# TIDA-00830_MSP430F2617.net
KiCad netlist of a schematic drawn in Altium Designer
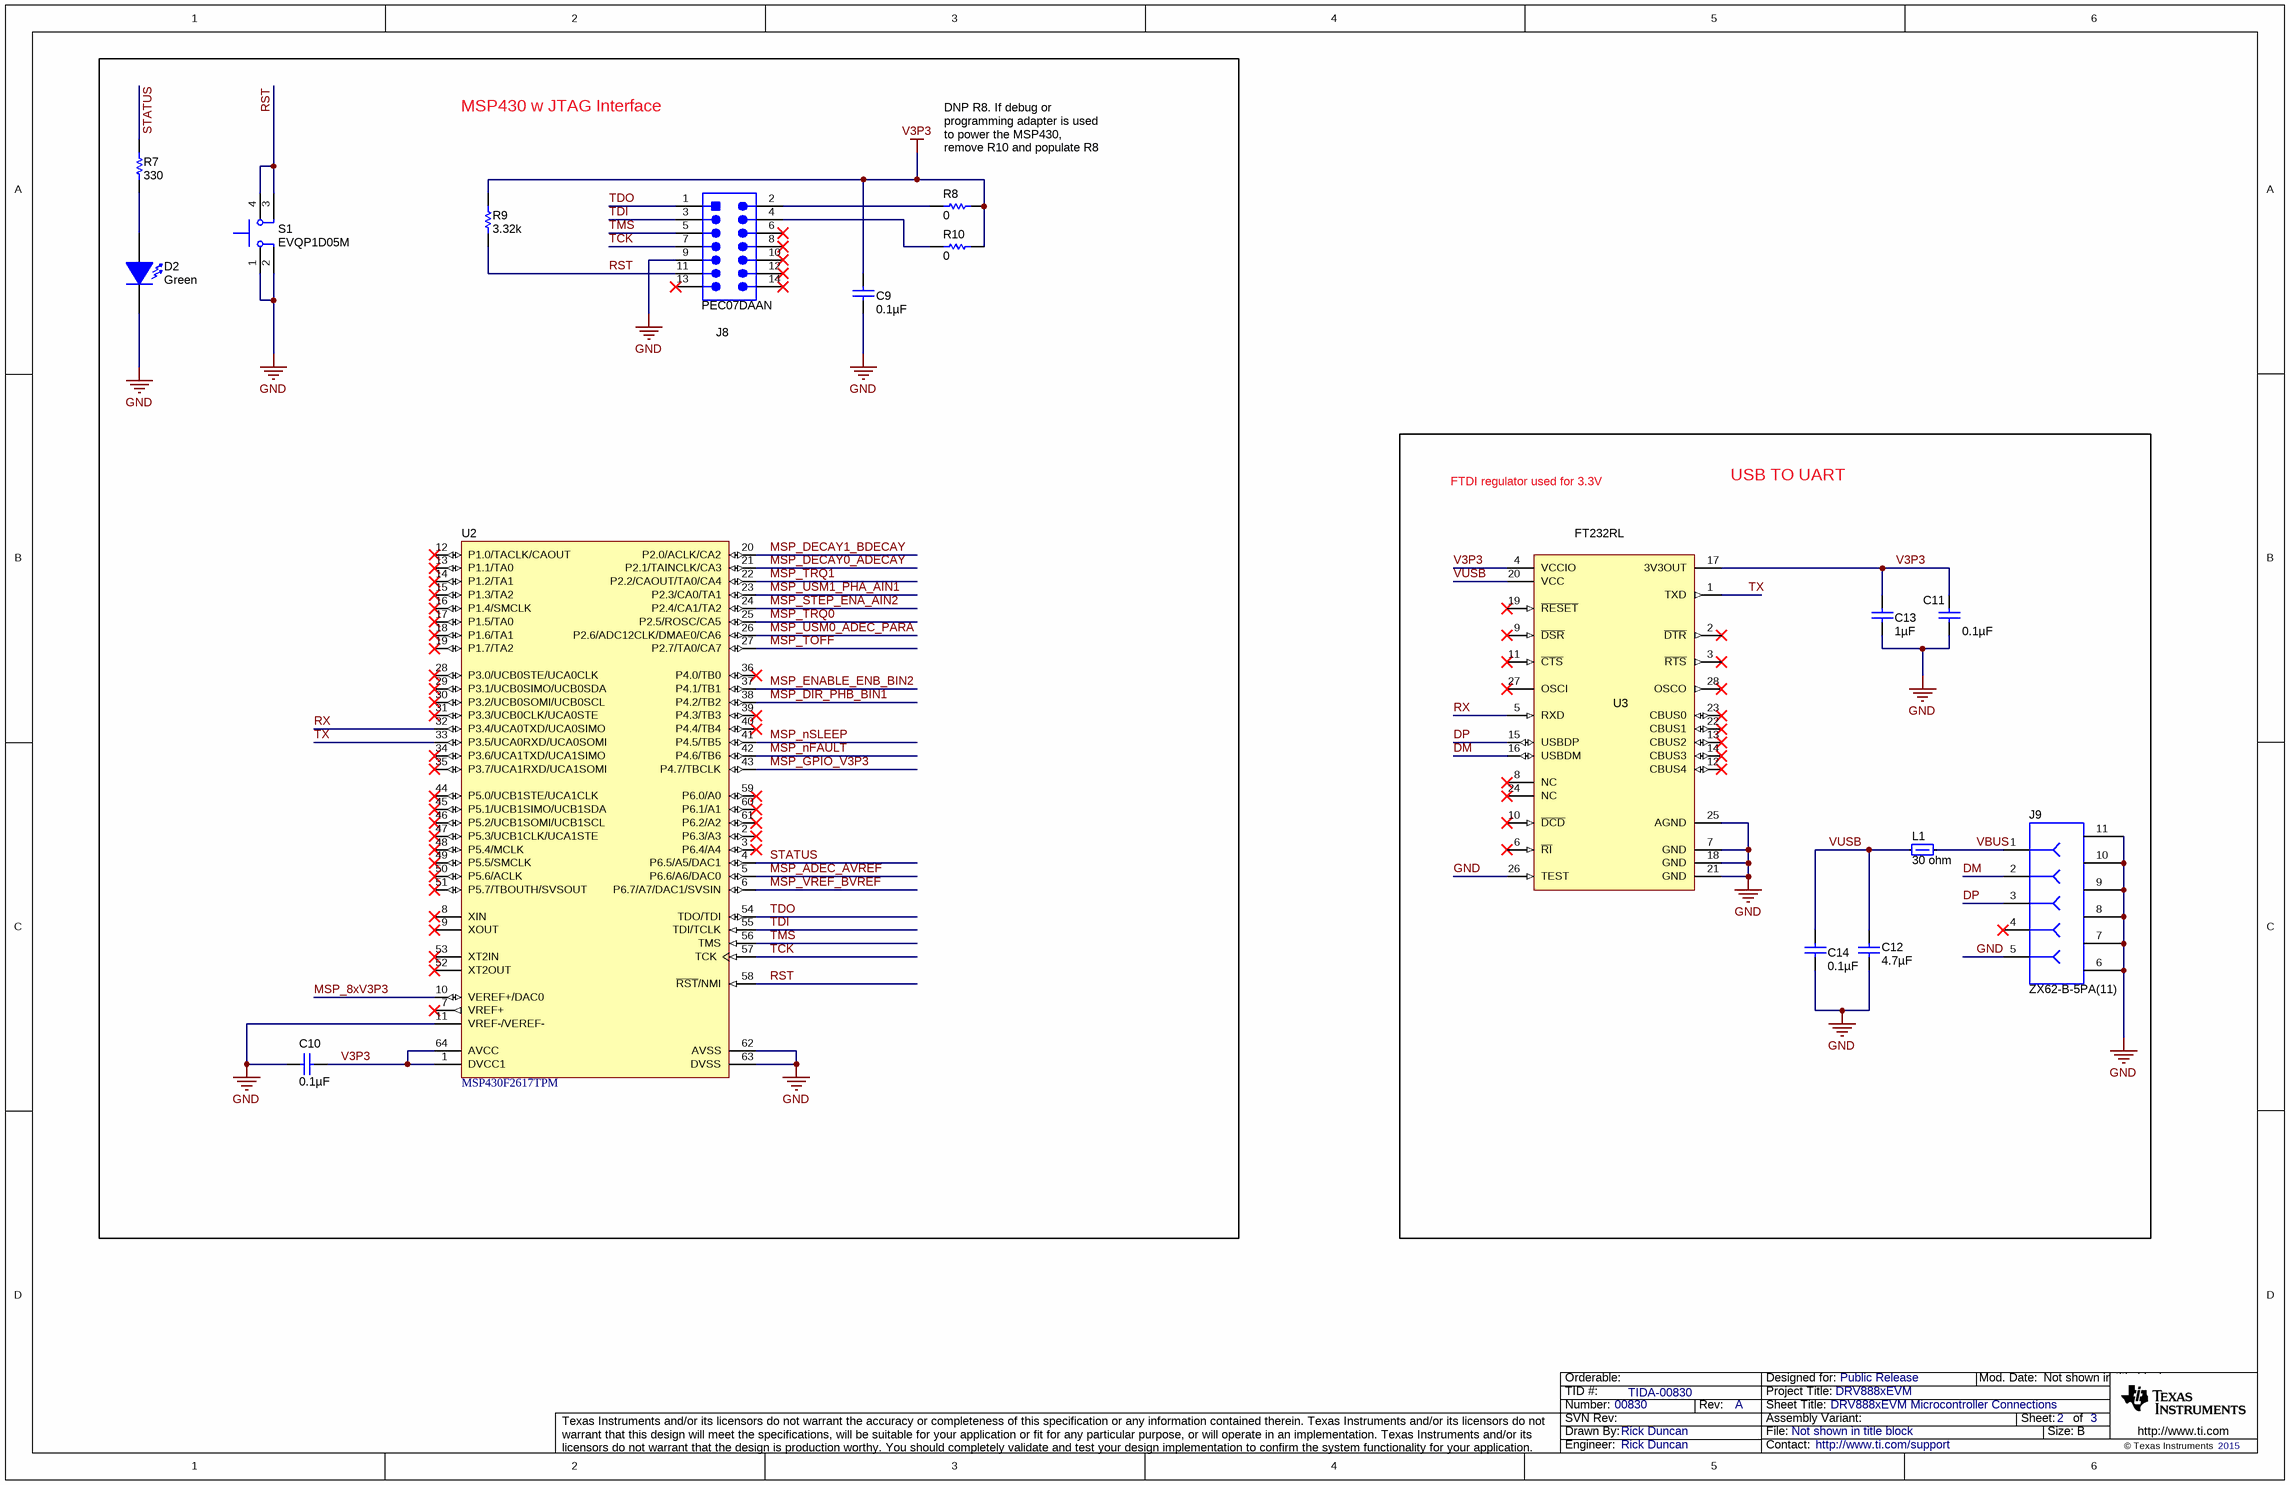
[diagram p0: TIDA-00830_MSP430F2617.SchDoc]

(export (version "E")
  (design (tool "Eeschema 10.0.6"))
  (components
    (comp (ref "C9")
      (value "GRM155R61A104KA01D")
      (footprint "0402L")
      (description "CAP, CERM, 0.1 µF, 10 V, +/- 10%, X5R, 0402")
      (fields
        (field (name "MANUFACTURER") "MuRata")
        (field (name "VALUEDISPLAYED") "0.1µF")
        (field (name "PUBLISHER") "Texas Instruments")
      )
      (libsource (lib "Capacitor_Ceramic") (part "GRM155R61A104KA01D"))
    )
    (comp (ref "C10")
      (value "GRM155R61A104KA01D")
      (footprint "0402L")
      (description "CAP, CERM, 0.1 µF, 10 V, +/- 10%, X5R, 0402")
      (fields
        (field (name "MANUFACTURER") "MuRata")
        (field (name "VALUEDISPLAYED") "0.1µF")
        (field (name "PUBLISHER") "Texas Instruments")
      )
      (libsource (lib "Capacitor_Ceramic") (part "GRM155R61A104KA01D"))
    )
    (comp (ref "C11")
      (value "GRM155R61A104KA01D")
      (footprint "0402L")
      (description "CAP, CERM, 0.1 µF, 10 V, +/- 10%, X5R, 0402")
      (fields
        (field (name "MANUFACTURER") "MuRata")
        (field (name "VALUEDISPLAYED") "0.1µF")
        (field (name "PUBLISHER") "Texas Instruments")
      )
      (libsource (lib "Capacitor_Ceramic") (part "GRM155R61A104KA01D"))
    )
    (comp (ref "C12")
      (value "CGB3B1X5R1A475K055AC")
      (footprint "0603L")
      (description "CAP, CERM, 4.7 µF, 10 V, +/- 10%, X5R, 0603")
      (fields
        (field (name "VALUEDISPLAYED") "4.7µF")
        (field (name "MANUFACTURER") "TDK")
        (field (name "PUBLISHER") "Texas Instruments")
      )
      (libsource (lib "Capacitor_Ceramic") (part "CGB3B1X5R1A475K055AC"))
    )
    (comp (ref "C13")
      (value "GRM155R61A105KE15D")
      (footprint "0402L")
      (description "CAP, CERM, 1 µF, 10 V, +/- 10%, X5R, 0402")
      (fields
        (field (name "MANUFACTURER") "MuRata")
        (field (name "VALUEDISPLAYED") "1µF")
        (field (name "PUBLISHER") "Texas Instruments")
      )
      (libsource (lib "Capacitor_Ceramic") (part "GRM155R61A105KE15D"))
    )
    (comp (ref "C14")
      (value "GRM155R61A104KA01D")
      (footprint "0402L")
      (description "CAP, CERM, 0.1 µF, 10 V, +/- 10%, X5R, 0402")
      (fields
        (field (name "MANUFACTURER") "MuRata")
        (field (name "VALUEDISPLAYED") "0.1µF")
        (field (name "PUBLISHER") "Texas Instruments")
      )
      (libsource (lib "Capacitor_Ceramic") (part "GRM155R61A104KA01D"))
    )
    (comp (ref "D2")
      (value "Green")
      (footprint "LED_LTST-C190")
      (description "LED, Green, SMD")
      (fields
        (field (name "MANUFACTURER") "Lite-On")
        (field (name "PARTNUMBER") "LTST-C190GKT")
        (field (name "PUBLISHER") "Texas Instruments")
      )
      (libsource (lib "LED") (part "LTST-C190GKT"))
    )
    (comp (ref "J8")
      (value "PEC07DAAN")
      (footprint "CONN_PEC07DAAN")
      (description "Header, 100mil, 7x2, Tin, TH")
      (fields
        (field (name "MANUFACTURER") "Sullins Connector Solutions")
        (field (name "SYMBOLCREATOR") "a0412235")
        (field (name "PUBLISHER") "Texas Instruments")
      )
      (libsource (lib "Connectors_Sullins") (part "PEC07DAAN"))
    )
    (comp (ref "J9")
      (value "ZX62-B-5PA(11)")
      (footprint "CONN_USB_micro_ZX62-B-5PA")
      (description "Connector, Receptacle, Micro-USB Type B, R/A, Bottom Mount SMT")
      (fields
        (field (name "MANUFACTURER") "Hirose Electric Co. Ltd.")
        (field (name "SYMBOLCREATOR") "a0411947")
        (field (name "PUBLISHER") "Texas Instruments")
      )
      (libsource (lib "Connectors_Other") (part "ZX62-B-5PA(11)"))
    )
    (comp (ref "L1")
      (value "30 ohm")
      (footprint "0805L")
      (description "Ferrite Bead, 30 ohm @ 100 MHz, 1.5 A, 0805")
      (fields
        (field (name "MANUFACTURER") "TDK")
        (field (name "PARTNUMBER") "MMZ2012R300A")
        (field (name "PUBLISHER") "Texas Instruments")
      )
      (libsource (lib "FerriteBead") (part "MMZ2012R300A"))
    )
    (comp (ref "R7")
      (value "330")
      (footprint "0402L")
      (description "RES, 330, 5%, 0.063 W, 0402")
      (fields
        (field (name "MANUFACTURER") "Vishay-Dale")
        (field (name "PARTNUMBER") "CRCW0402330RJNED")
        (field (name "PUBLISHER") "Texas Instruments")
      )
      (libsource (lib "Resistor_0402") (part "CRCW0402330RJNED"))
    )
    (comp (ref "R8")
      (value "0")
      (footprint "0402L")
      (description "RES, 0, 5%, 0.063 W, 0402")
      (fields
        (field (name "MANUFACTURER") "Panasonic")
        (field (name "PARTNUMBER") "ERJ-2GE0R00X")
        (field (name "PUBLISHER") "Texas Instruments")
      )
      (libsource (lib "Resistor_0402") (part "ERJ-2GE0R00X"))
    )
    (comp (ref "R9")
      (value "3.32k")
      (footprint "0402L")
      (description "RES, 3.32 k, 1%, 0.063 W, 0402")
      (fields
        (field (name "MANUFACTURER") "Vishay-Dale")
        (field (name "PARTNUMBER") "CRCW04023K32FKED")
        (field (name "PUBLISHER") "Texas Instruments")
      )
      (libsource (lib "Resistor_0402") (part "CRCW04023K32FKED"))
    )
    (comp (ref "R10")
      (value "0")
      (footprint "0402L")
      (description "RES, 0, 5%, 0.063 W, 0402")
      (fields
        (field (name "MANUFACTURER") "Panasonic")
        (field (name "PARTNUMBER") "ERJ-2GE0R00X")
        (field (name "PUBLISHER") "Texas Instruments")
      )
      (libsource (lib "Resistor_0402") (part "ERJ-2GE0R00X"))
    )
    (comp (ref "S1")
      (value "EVQP1D05M")
      (footprint "SW_EVQxxx05M")
      (description "Switch, Tactile, SPST-NO, 0.05A, 12V, SMT")
      (fields
        (field (name "MANUFACTURER") "Panasonic")
        (field (name "SYMBOLCREATOR") "a0799628")
        (field (name "PUBLISHER") "Texas Instruments")
      )
      (libsource (lib "Switches") (part "EVQP1D05M"))
    )
    (comp (ref "U2")
      (value "MSP430F2617TPM")
      (footprint "PM0064A_L")
      (fields
        (field (name "MANUFACTURER") "Texas Instruments")
        (field (name "ALTERNATE PARTNUMBER") "Equivalent")
      )
      (libsource (lib "TI MCU MSP430") (part "MSP430F2617TPM"))
    )
    (comp (ref "U3")
      (value "FT232RL")
      (footprint "SSOP28_M")
      (description "USB to Serial UART, SSOP28")
      (fields
        (field (name "MANUFACTURER") "FTDI")
        (field (name "SYMBOLCREATOR") "x0208326")
        (field (name "PUBLISHER") "Texas Instruments")
      )
      (libsource (lib "Other_IC") (part "FT232RL"))
    )
  )
  (nets
    (net (code "1") (name "/DM") (class "Default")
      (node (ref "J9") (pin "2") (pinfunction "2_2") (pintype "passive"))
      (node (ref "U3") (pin "16") (pinfunction "USBDM_16") (pintype "bidirectional"))
    )
    (net (code "2") (name "/DP") (class "Default")
      (node (ref "J9") (pin "3") (pinfunction "3_3") (pintype "passive"))
      (node (ref "U3") (pin "15") (pinfunction "USBDP_15") (pintype "bidirectional"))
    )
    (net (code "3") (name "/MSP_8xV3P3") (class "Default")
      (node (ref "U2") (pin "10") (pinfunction "VEREF+/DAC0_10") (pintype "bidirectional"))
    )
    (net (code "4") (name "/MSP_ADEC_AVREF") (class "Default")
      (node (ref "U2") (pin "5") (pinfunction "P6.6/A6/DAC0_5") (pintype "bidirectional"))
    )
    (net (code "5") (name "/MSP_DECAY0_ADECAY") (class "Default")
      (node (ref "U2") (pin "21") (pinfunction "P2.1/TAINCLK/CA3_21") (pintype "bidirectional"))
    )
    (net (code "6") (name "/MSP_DECAY1_BDECAY") (class "Default")
      (node (ref "U2") (pin "20") (pinfunction "P2.0/ACLK/CA2_20") (pintype "bidirectional"))
    )
    (net (code "7") (name "/MSP_DIR_PHB_BIN1") (class "Default")
      (node (ref "U2") (pin "38") (pinfunction "P4.2/TB2_38") (pintype "bidirectional"))
    )
    (net (code "8") (name "/MSP_ENABLE_ENB_BIN2") (class "Default")
      (node (ref "U2") (pin "37") (pinfunction "P4.1/TB1_37") (pintype "bidirectional"))
    )
    (net (code "9") (name "/MSP_GPIO_V3P3") (class "Default")
      (node (ref "U2") (pin "43") (pinfunction "P4.7/TBCLK_43") (pintype "bidirectional"))
    )
    (net (code "10") (name "/MSP_STEP_ENA_AIN2") (class "Default")
      (node (ref "U2") (pin "24") (pinfunction "P2.4/CA1/TA2_24") (pintype "bidirectional"))
    )
    (net (code "11") (name "/MSP_TOFF") (class "Default")
      (node (ref "U2") (pin "27") (pinfunction "P2.7/TA0/CA7_27") (pintype "bidirectional"))
    )
    (net (code "12") (name "/MSP_TRQ0") (class "Default")
      (node (ref "U2") (pin "25") (pinfunction "P2.5/ROSC/CA5_25") (pintype "bidirectional"))
    )
    (net (code "13") (name "/MSP_TRQ1") (class "Default")
      (node (ref "U2") (pin "22") (pinfunction "P2.2/CAOUT/TA0/CA4_22") (pintype "bidirectional"))
    )
    (net (code "14") (name "/MSP_USM0_ADEC_PARA") (class "Default")
      (node (ref "U2") (pin "26") (pinfunction "P2.6/ADC12CLK/DMAE0/CA6_26") (pintype "bidirectional"))
    )
    (net (code "15") (name "/MSP_USM1_PHA_AIN1") (class "Default")
      (node (ref "U2") (pin "23") (pinfunction "P2.3/CA0/TA1_23") (pintype "bidirectional"))
    )
    (net (code "16") (name "/MSP_VREF_BVREF") (class "Default")
      (node (ref "U2") (pin "6") (pinfunction "P6.7/A7/DAC1/SVSIN_6") (pintype "bidirectional"))
    )
    (net (code "17") (name "/MSP_nFAULT") (class "Default")
      (node (ref "U2") (pin "42") (pinfunction "P4.6/TB6_42") (pintype "bidirectional"))
    )
    (net (code "18") (name "/MSP_nSLEEP") (class "Default")
      (node (ref "U2") (pin "41") (pinfunction "P4.5/TB5_41") (pintype "bidirectional"))
    )
    (net (code "19") (name "/RST") (class "Default")
      (node (ref "J8") (pin "11") (pinfunction "11_11") (pintype "passive"))
      (node (ref "R9") (pin "1") (pinfunction "1_1") (pintype "passive"))
      (node (ref "S1") (pin "3") (pinfunction "3_3") (pintype "passive"))
      (node (ref "S1") (pin "4") (pinfunction "4_4") (pintype "passive"))
      (node (ref "U2") (pin "58") (pinfunction "~{RST}/NMI_58") (pintype "input"))
    )
    (net (code "20") (name "/RX") (class "Default")
      (node (ref "U2") (pin "32") (pinfunction "P3.4/UCA0TXD/UCA0SIMO_32") (pintype "bidirectional"))
      (node (ref "U3") (pin "5") (pinfunction "RXD_5") (pintype "input"))
    )
    (net (code "21") (name "/STATUS") (class "Default")
      (node (ref "R7") (pin "2") (pinfunction "2_2") (pintype "passive"))
      (node (ref "U2") (pin "4") (pinfunction "P6.5/A5/DAC1_4") (pintype "bidirectional"))
    )
    (net (code "22") (name "/TCK") (class "Default")
      (node (ref "J8") (pin "7") (pinfunction "7_7") (pintype "passive"))
      (node (ref "U2") (pin "57") (pinfunction "TCK_57") (pintype "input"))
    )
    (net (code "23") (name "/TDI") (class "Default")
      (node (ref "J8") (pin "3") (pinfunction "3_3") (pintype "passive"))
      (node (ref "U2") (pin "55") (pinfunction "TDI/TCLK_55") (pintype "input"))
    )
    (net (code "24") (name "/TDO") (class "Default")
      (node (ref "J8") (pin "1") (pinfunction "1_1") (pintype "passive"))
      (node (ref "U2") (pin "54") (pinfunction "TDO/TDI_54") (pintype "bidirectional"))
    )
    (net (code "25") (name "/TMS") (class "Default")
      (node (ref "J8") (pin "5") (pinfunction "5_5") (pintype "passive"))
      (node (ref "U2") (pin "56") (pinfunction "TMS_56") (pintype "input"))
    )
    (net (code "26") (name "/TX") (class "Default")
      (node (ref "U2") (pin "33") (pinfunction "P3.5/UCA0RXD/UCA0SOMI_33") (pintype "bidirectional"))
      (node (ref "U3") (pin "1") (pinfunction "TXD_1") (pintype "output"))
    )
    (net (code "27") (name "/VBUS") (class "Default")
      (node (ref "J9") (pin "1") (pinfunction "1_1") (pintype "passive"))
      (node (ref "L1") (pin "2") (pinfunction "2_2") (pintype "passive"))
    )
    (net (code "28") (name "/VUSB") (class "Default")
      (node (ref "C12") (pin "1") (pinfunction "1_1") (pintype "passive"))
      (node (ref "C14") (pin "1") (pinfunction "1_1") (pintype "passive"))
      (node (ref "L1") (pin "1") (pinfunction "1_1") (pintype "passive"))
      (node (ref "U3") (pin "20") (pinfunction "VCC_20") (pintype "power_in"))
    )
    (net (code "29") (name "GND") (class "Default")
      (node (ref "C10") (pin "2") (pinfunction "2_2") (pintype "passive"))
      (node (ref "C11") (pin "2") (pinfunction "2_2") (pintype "passive"))
      (node (ref "C12") (pin "2") (pinfunction "2_2") (pintype "passive"))
      (node (ref "C13") (pin "2") (pinfunction "2_2") (pintype "passive"))
      (node (ref "C14") (pin "2") (pinfunction "2_2") (pintype "passive"))
      (node (ref "C9") (pin "2") (pinfunction "2_2") (pintype "passive"))
      (node (ref "D2") (pin "2") (pinfunction "K_2") (pintype "passive"))
      (node (ref "J8") (pin "9") (pinfunction "9_9") (pintype "passive"))
      (node (ref "J9") (pin "10") (pinfunction "10_10") (pintype "passive"))
      (node (ref "J9") (pin "11") (pinfunction "11_11") (pintype "passive"))
      (node (ref "J9") (pin "5") (pinfunction "5_5") (pintype "passive"))
      (node (ref "J9") (pin "6") (pinfunction "6_6") (pintype "passive"))
      (node (ref "J9") (pin "7") (pinfunction "7_7") (pintype "passive"))
      (node (ref "J9") (pin "8") (pinfunction "8_8") (pintype "passive"))
      (node (ref "J9") (pin "9") (pinfunction "9_9") (pintype "passive"))
      (node (ref "S1") (pin "1") (pinfunction "1_1") (pintype "passive"))
      (node (ref "S1") (pin "2") (pinfunction "2_2") (pintype "passive"))
      (node (ref "U2") (pin "11") (pinfunction "VREF-/VEREF-_11") (pintype "passive"))
      (node (ref "U2") (pin "62") (pinfunction "AVSS_62") (pintype "power_in"))
      (node (ref "U2") (pin "63") (pinfunction "DVSS_63") (pintype "power_in"))
      (node (ref "U3") (pin "18") (pinfunction "GND_18") (pintype "power_in"))
      (node (ref "U3") (pin "21") (pinfunction "GND_21") (pintype "power_in"))
      (node (ref "U3") (pin "25") (pinfunction "AGND_25") (pintype "power_in"))
      (node (ref "U3") (pin "26") (pinfunction "TEST_26") (pintype "input"))
      (node (ref "U3") (pin "7") (pinfunction "GND_7") (pintype "power_in"))
    )
    (net (code "30") (name "Net-(D2-A)") (class "Default")
      (node (ref "D2") (pin "1") (pinfunction "A_1") (pintype "passive"))
      (node (ref "R7") (pin "1") (pinfunction "1_1") (pintype "passive"))
    )
    (net (code "31") (name "Net-(J8-Pad2)") (class "Default")
      (node (ref "J8") (pin "2") (pinfunction "2_2") (pintype "passive"))
      (node (ref "R8") (pin "2") (pinfunction "2_2") (pintype "passive"))
    )
    (net (code "32") (name "Net-(J8-Pad4)") (class "Default")
      (node (ref "J8") (pin "4") (pinfunction "4_4") (pintype "passive"))
      (node (ref "R10") (pin "2") (pinfunction "2_2") (pintype "passive"))
    )
    (net (code "33") (name "V3P3") (class "Default")
      (node (ref "C10") (pin "1") (pinfunction "1_1") (pintype "passive"))
      (node (ref "C11") (pin "1") (pinfunction "1_1") (pintype "passive"))
      (node (ref "C13") (pin "1") (pinfunction "1_1") (pintype "passive"))
      (node (ref "C9") (pin "1") (pinfunction "1_1") (pintype "passive"))
      (node (ref "R10") (pin "1") (pinfunction "1_1") (pintype "passive"))
      (node (ref "R8") (pin "1") (pinfunction "1_1") (pintype "passive"))
      (node (ref "R9") (pin "2") (pinfunction "2_2") (pintype "passive"))
      (node (ref "U2") (pin "1") (pinfunction "DVCC1_1") (pintype "power_in"))
      (node (ref "U2") (pin "64") (pinfunction "AVCC_64") (pintype "power_in"))
      (node (ref "U3") (pin "17") (pinfunction "3V3OUT_17") (pintype "power_in"))
      (node (ref "U3") (pin "4") (pinfunction "VCCIO_4") (pintype "power_in"))
    )
    (net (code "34") (name "unconnected-(J8-Pad6)") (class "Default")
      (node (ref "J8") (pin "6") (pinfunction "6_6") (pintype "passive+no_connect"))
    )
    (net (code "35") (name "unconnected-(J8-Pad8)") (class "Default")
      (node (ref "J8") (pin "8") (pinfunction "8_8") (pintype "passive+no_connect"))
    )
    (net (code "36") (name "unconnected-(J8-Pad10)") (class "Default")
      (node (ref "J8") (pin "10") (pinfunction "10_10") (pintype "passive+no_connect"))
    )
    (net (code "37") (name "unconnected-(J8-Pad12)") (class "Default")
      (node (ref "J8") (pin "12") (pinfunction "12_12") (pintype "passive+no_connect"))
    )
    (net (code "38") (name "unconnected-(J8-Pad13)") (class "Default")
      (node (ref "J8") (pin "13") (pinfunction "13_13") (pintype "passive+no_connect"))
    )
    (net (code "39") (name "unconnected-(J8-Pad14)") (class "Default")
      (node (ref "J8") (pin "14") (pinfunction "14_14") (pintype "passive+no_connect"))
    )
    (net (code "40") (name "unconnected-(J9-Pad4)") (class "Default")
      (node (ref "J9") (pin "4") (pinfunction "4_4") (pintype "passive+no_connect"))
    )
    (net (code "41") (name "unconnected-(U2-P1.0{slash}TACLK{slash}CAOUT-Pad12)") (class "Default")
      (node (ref "U2") (pin "12") (pinfunction "P1.0/TACLK/CAOUT_12") (pintype "bidirectional+no_connect"))
    )
    (net (code "42") (name "unconnected-(U2-P1.1{slash}TA0-Pad13)") (class "Default")
      (node (ref "U2") (pin "13") (pinfunction "P1.1/TA0_13") (pintype "bidirectional+no_connect"))
    )
    (net (code "43") (name "unconnected-(U2-P1.2{slash}TA1-Pad14)") (class "Default")
      (node (ref "U2") (pin "14") (pinfunction "P1.2/TA1_14") (pintype "bidirectional+no_connect"))
    )
    (net (code "44") (name "unconnected-(U2-P1.3{slash}TA2-Pad15)") (class "Default")
      (node (ref "U2") (pin "15") (pinfunction "P1.3/TA2_15") (pintype "bidirectional+no_connect"))
    )
    (net (code "45") (name "unconnected-(U2-P1.4{slash}SMCLK-Pad16)") (class "Default")
      (node (ref "U2") (pin "16") (pinfunction "P1.4/SMCLK_16") (pintype "bidirectional+no_connect"))
    )
    (net (code "46") (name "unconnected-(U2-P1.5{slash}TA0-Pad17)") (class "Default")
      (node (ref "U2") (pin "17") (pinfunction "P1.5/TA0_17") (pintype "bidirectional+no_connect"))
    )
    (net (code "47") (name "unconnected-(U2-P1.6{slash}TA1-Pad18)") (class "Default")
      (node (ref "U2") (pin "18") (pinfunction "P1.6/TA1_18") (pintype "bidirectional+no_connect"))
    )
    (net (code "48") (name "unconnected-(U2-P1.7{slash}TA2-Pad19)") (class "Default")
      (node (ref "U2") (pin "19") (pinfunction "P1.7/TA2_19") (pintype "bidirectional+no_connect"))
    )
    (net (code "49") (name "unconnected-(U2-P3.0{slash}UCB0STE{slash}UCA0CLK-Pad28)") (class "Default")
      (node (ref "U2") (pin "28") (pinfunction "P3.0/UCB0STE/UCA0CLK_28") (pintype "bidirectional+no_connect"))
    )
    (net (code "50") (name "unconnected-(U2-P3.1{slash}UCB0SIMO{slash}UCB0SDA-Pad29)") (class "Default")
      (node (ref "U2") (pin "29") (pinfunction "P3.1/UCB0SIMO/UCB0SDA_29") (pintype "bidirectional+no_connect"))
    )
    (net (code "51") (name "unconnected-(U2-P3.2{slash}UCB0SOMI{slash}UCB0SCL-Pad30)") (class "Default")
      (node (ref "U2") (pin "30") (pinfunction "P3.2/UCB0SOMI/UCB0SCL_30") (pintype "bidirectional+no_connect"))
    )
    (net (code "52") (name "unconnected-(U2-P3.3{slash}UCB0CLK{slash}UCA0STE-Pad31)") (class "Default")
      (node (ref "U2") (pin "31") (pinfunction "P3.3/UCB0CLK/UCA0STE_31") (pintype "bidirectional+no_connect"))
    )
    (net (code "53") (name "unconnected-(U2-P3.6{slash}UCA1TXD{slash}UCA1SIMO-Pad34)") (class "Default")
      (node (ref "U2") (pin "34") (pinfunction "P3.6/UCA1TXD/UCA1SIMO_34") (pintype "bidirectional+no_connect"))
    )
    (net (code "54") (name "unconnected-(U2-P3.7{slash}UCA1RXD{slash}UCA1SOMI-Pad35)") (class "Default")
      (node (ref "U2") (pin "35") (pinfunction "P3.7/UCA1RXD/UCA1SOMI_35") (pintype "bidirectional+no_connect"))
    )
    (net (code "55") (name "unconnected-(U2-P4.0{slash}TB0-Pad36)") (class "Default")
      (node (ref "U2") (pin "36") (pinfunction "P4.0/TB0_36") (pintype "bidirectional+no_connect"))
    )
    (net (code "56") (name "unconnected-(U2-P4.3{slash}TB3-Pad39)") (class "Default")
      (node (ref "U2") (pin "39") (pinfunction "P4.3/TB3_39") (pintype "bidirectional+no_connect"))
    )
    (net (code "57") (name "unconnected-(U2-P4.4{slash}TB4-Pad40)") (class "Default")
      (node (ref "U2") (pin "40") (pinfunction "P4.4/TB4_40") (pintype "bidirectional+no_connect"))
    )
    (net (code "58") (name "unconnected-(U2-P5.0{slash}UCB1STE{slash}UCA1CLK-Pad44)") (class "Default")
      (node (ref "U2") (pin "44") (pinfunction "P5.0/UCB1STE/UCA1CLK_44") (pintype "bidirectional+no_connect"))
    )
    (net (code "59") (name "unconnected-(U2-P5.1{slash}UCB1SIMO{slash}UCB1SDA-Pad45)") (class "Default")
      (node (ref "U2") (pin "45") (pinfunction "P5.1/UCB1SIMO/UCB1SDA_45") (pintype "bidirectional+no_connect"))
    )
    (net (code "60") (name "unconnected-(U2-P5.2{slash}UCB1SOMI{slash}UCB1SCL-Pad46)") (class "Default")
      (node (ref "U2") (pin "46") (pinfunction "P5.2/UCB1SOMI/UCB1SCL_46") (pintype "bidirectional+no_connect"))
    )
    (net (code "61") (name "unconnected-(U2-P5.3{slash}UCB1CLK{slash}UCA1STE-Pad47)") (class "Default")
      (node (ref "U2") (pin "47") (pinfunction "P5.3/UCB1CLK/UCA1STE_47") (pintype "bidirectional+no_connect"))
    )
    (net (code "62") (name "unconnected-(U2-P5.4{slash}MCLK-Pad48)") (class "Default")
      (node (ref "U2") (pin "48") (pinfunction "P5.4/MCLK_48") (pintype "bidirectional+no_connect"))
    )
    (net (code "63") (name "unconnected-(U2-P5.5{slash}SMCLK-Pad49)") (class "Default")
      (node (ref "U2") (pin "49") (pinfunction "P5.5/SMCLK_49") (pintype "bidirectional+no_connect"))
    )
    (net (code "64") (name "unconnected-(U2-P5.6{slash}ACLK-Pad50)") (class "Default")
      (node (ref "U2") (pin "50") (pinfunction "P5.6/ACLK_50") (pintype "bidirectional+no_connect"))
    )
    (net (code "65") (name "unconnected-(U2-P5.7{slash}TBOUTH{slash}SVSOUT-Pad51)") (class "Default")
      (node (ref "U2") (pin "51") (pinfunction "P5.7/TBOUTH/SVSOUT_51") (pintype "bidirectional+no_connect"))
    )
    (net (code "66") (name "unconnected-(U2-P6.0{slash}A0-Pad59)") (class "Default")
      (node (ref "U2") (pin "59") (pinfunction "P6.0/A0_59") (pintype "bidirectional+no_connect"))
    )
    (net (code "67") (name "unconnected-(U2-P6.1{slash}A1-Pad60)") (class "Default")
      (node (ref "U2") (pin "60") (pinfunction "P6.1/A1_60") (pintype "bidirectional+no_connect"))
    )
    (net (code "68") (name "unconnected-(U2-P6.2{slash}A2-Pad61)") (class "Default")
      (node (ref "U2") (pin "61") (pinfunction "P6.2/A2_61") (pintype "bidirectional+no_connect"))
    )
    (net (code "69") (name "unconnected-(U2-P6.3{slash}A3-Pad2)") (class "Default")
      (node (ref "U2") (pin "2") (pinfunction "P6.3/A3_2") (pintype "bidirectional+no_connect"))
    )
    (net (code "70") (name "unconnected-(U2-P6.4{slash}A4-Pad3)") (class "Default")
      (node (ref "U2") (pin "3") (pinfunction "P6.4/A4_3") (pintype "bidirectional+no_connect"))
    )
    (net (code "71") (name "unconnected-(U2-VREF+-Pad7)") (class "Default")
      (node (ref "U2") (pin "7") (pinfunction "VREF+_7") (pintype "output+no_connect"))
    )
    (net (code "72") (name "unconnected-(U2-XIN-Pad8)") (class "Default")
      (node (ref "U2") (pin "8") (pinfunction "XIN_8") (pintype "passive+no_connect"))
    )
    (net (code "73") (name "unconnected-(U2-XOUT-Pad9)") (class "Default")
      (node (ref "U2") (pin "9") (pinfunction "XOUT_9") (pintype "passive+no_connect"))
    )
    (net (code "74") (name "unconnected-(U2-XT2IN-Pad53)") (class "Default")
      (node (ref "U2") (pin "53") (pinfunction "XT2IN_53") (pintype "passive+no_connect"))
    )
    (net (code "75") (name "unconnected-(U2-XT2OUT-Pad52)") (class "Default")
      (node (ref "U2") (pin "52") (pinfunction "XT2OUT_52") (pintype "passive+no_connect"))
    )
    (net (code "76") (name "unconnected-(U3-CBUS0-Pad23)") (class "Default")
      (node (ref "U3") (pin "23") (pinfunction "CBUS0_23") (pintype "bidirectional+no_connect"))
    )
    (net (code "77") (name "unconnected-(U3-CBUS1-Pad22)") (class "Default")
      (node (ref "U3") (pin "22") (pinfunction "CBUS1_22") (pintype "bidirectional+no_connect"))
    )
    (net (code "78") (name "unconnected-(U3-CBUS2-Pad13)") (class "Default")
      (node (ref "U3") (pin "13") (pinfunction "CBUS2_13") (pintype "bidirectional+no_connect"))
    )
    (net (code "79") (name "unconnected-(U3-CBUS3-Pad14)") (class "Default")
      (node (ref "U3") (pin "14") (pinfunction "CBUS3_14") (pintype "bidirectional+no_connect"))
    )
    (net (code "80") (name "unconnected-(U3-CBUS4-Pad12)") (class "Default")
      (node (ref "U3") (pin "12") (pinfunction "CBUS4_12") (pintype "bidirectional+no_connect"))
    )
    (net (code "81") (name "unconnected-(U3-CTS-Pad11)") (class "Default")
      (node (ref "U3") (pin "11") (pinfunction "CTS_11") (pintype "input+no_connect"))
    )
    (net (code "82") (name "unconnected-(U3-DCD-Pad10)") (class "Default")
      (node (ref "U3") (pin "10") (pinfunction "DCD_10") (pintype "input+no_connect"))
    )
    (net (code "83") (name "unconnected-(U3-DSR-Pad9)") (class "Default")
      (node (ref "U3") (pin "9") (pinfunction "DSR_9") (pintype "input+no_connect"))
    )
    (net (code "84") (name "unconnected-(U3-DTR-Pad2)") (class "Default")
      (node (ref "U3") (pin "2") (pinfunction "DTR_2") (pintype "output+no_connect"))
    )
    (net (code "85") (name "unconnected-(U3-NC-Pad8)") (class "Default")
      (node (ref "U3") (pin "8") (pinfunction "NC_8") (pintype "passive+no_connect"))
    )
    (net (code "86") (name "unconnected-(U3-NC-Pad24)") (class "Default")
      (node (ref "U3") (pin "24") (pinfunction "NC_24") (pintype "passive+no_connect"))
    )
    (net (code "87") (name "unconnected-(U3-OSCI-Pad27)") (class "Default")
      (node (ref "U3") (pin "27") (pinfunction "OSCI_27") (pintype "passive+no_connect"))
    )
    (net (code "88") (name "unconnected-(U3-OSCO-Pad28)") (class "Default")
      (node (ref "U3") (pin "28") (pinfunction "OSCO_28") (pintype "output+no_connect"))
    )
    (net (code "89") (name "unconnected-(U3-RESET-Pad19)") (class "Default")
      (node (ref "U3") (pin "19") (pinfunction "RESET_19") (pintype "input+no_connect"))
    )
    (net (code "90") (name "unconnected-(U3-RI-Pad6)") (class "Default")
      (node (ref "U3") (pin "6") (pinfunction "RI_6") (pintype "input+no_connect"))
    )
    (net (code "91") (name "unconnected-(U3-RTS-Pad3)") (class "Default")
      (node (ref "U3") (pin "3") (pinfunction "RTS_3") (pintype "output+no_connect"))
    )
  )
)
